# 5_to_var_new.net
KiCad netlist of a schematic drawn in EAGLE
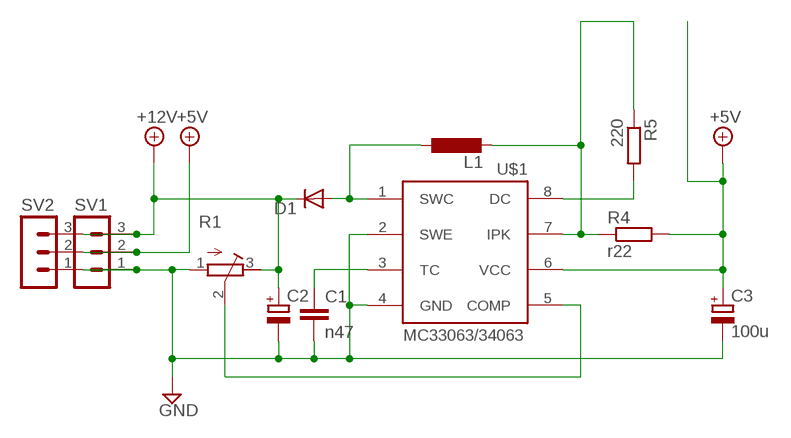
[diagram p0: schematic, sheet 1]

(export (version "E")
  (design (tool "Eeschema 10.0.6"))
  (components
    (comp (ref "C1")
      (value "n47")
      (footprint "eagle-import:C025-025X050")
      (libsource (lib "eagle-import") (part "C-EU025-025X050"))
    )
    (comp (ref "C2")
      (value "CPOL-EUE3.5-8")
      (footprint "eagle-import:E3,5-8")
      (libsource (lib "eagle-import") (part "CPOL-EUE3.5-8"))
    )
    (comp (ref "C3")
      (value "100u")
      (footprint "eagle-import:E2,5-7")
      (libsource (lib "eagle-import") (part "CPOL-EUE2.5-7"))
    )
    (comp (ref "D1")
      (value "DIODE-D-2.5")
      (footprint "eagle-import:D-2.5")
      (libsource (lib "eagle-import") (part "DIODE-D-2.5"))
    )
    (comp (ref "L1")
      (value "L-EU0207/2V")
      (footprint "eagle-import:0207_2V")
      (libsource (lib "eagle-import") (part "L-EU0207/2V"))
    )
    (comp (ref "R1")
      (value "R-TRIMM3296X")
      (footprint "eagle-import:RTRIM3296X")
      (libsource (lib "eagle-import") (part "R-TRIMM3296X"))
    )
    (comp (ref "R4")
      (value "r22")
      (footprint "eagle-import:0207_2V")
      (libsource (lib "eagle-import") (part "R-EU_0207/2V"))
    )
    (comp (ref "R5")
      (value "220")
      (footprint "eagle-import:0207_2V")
      (libsource (lib "eagle-import") (part "R-EU_0207/2V"))
    )
    (comp (ref "SV1")
      (value "MA03-1")
      (footprint "eagle-import:MA03-1")
      (libsource (lib "eagle-import") (part "MA03-1"))
    )
    (comp (ref "SV2")
      (value "MA03-1")
      (footprint "eagle-import:MA03-1")
      (libsource (lib "eagle-import") (part "MA03-1"))
    )
    (comp (ref "U$1")
      (value "MC33063/MC34063P")
      (footprint "eagle-import:DIL08")
      (libsource (lib "eagle-import") (part "MC33063/MC34063P"))
    )
  )
  (nets
    (net (code "1") (name "+5V") (class "Default")
      (node (ref "C3") (pin "+") (pinfunction "+_+") (pintype "passive"))
      (node (ref "R4") (pin "2") (pinfunction "2_2") (pintype "passive"))
      (node (ref "SV1") (pin "2") (pinfunction "2_2") (pintype "passive"))
      (node (ref "SV2") (pin "2") (pinfunction "2_2") (pintype "passive"))
      (node (ref "U$1") (pin "6") (pinfunction "VCC_6") (pintype "power_in"))
    )
    (net (code "2") (name "+12V") (class "Default")
      (node (ref "C2") (pin "+") (pinfunction "+_+") (pintype "passive"))
      (node (ref "D1") (pin "C") (pinfunction "C_C") (pintype "passive"))
      (node (ref "R1") (pin "3") (pinfunction "E_3") (pintype "passive"))
      (node (ref "SV1") (pin "3") (pinfunction "3_3") (pintype "passive"))
      (node (ref "SV2") (pin "3") (pinfunction "3_3") (pintype "passive"))
    )
    (net (code "3") (name "GND") (class "Default")
      (node (ref "C1") (pin "2") (pinfunction "2_2") (pintype "passive"))
      (node (ref "C2") (pin "-") (pinfunction "-_-") (pintype "passive"))
      (node (ref "C3") (pin "-") (pinfunction "-_-") (pintype "passive"))
      (node (ref "R1") (pin "1") (pinfunction "A_1") (pintype "passive"))
      (node (ref "SV1") (pin "1") (pinfunction "1_1") (pintype "passive"))
      (node (ref "SV2") (pin "1") (pinfunction "1_1") (pintype "passive"))
      (node (ref "U$1") (pin "2") (pinfunction "SWE_2") (pintype "input"))
      (node (ref "U$1") (pin "4") (pinfunction "GND_4") (pintype "power_in"))
    )
    (net (code "4") (name "Net-(R1-S)") (class "Default")
      (node (ref "R1") (pin "2") (pinfunction "S_2") (pintype "passive"))
      (node (ref "U$1") (pin "5") (pinfunction "COMP_5") (pintype "input"))
    )
    (net (code "5") (name "Net-(U$1-DC)") (class "Default")
      (node (ref "R5") (pin "2") (pinfunction "2_2") (pintype "passive"))
      (node (ref "U$1") (pin "8") (pinfunction "DC_8") (pintype "input"))
    )
    (net (code "6") (name "Net-(U$1-IPK)") (class "Default")
      (node (ref "L1") (pin "2") (pinfunction "2_2") (pintype "passive"))
      (node (ref "R4") (pin "1") (pinfunction "1_1") (pintype "passive"))
      (node (ref "R5") (pin "1") (pinfunction "1_1") (pintype "passive"))
      (node (ref "U$1") (pin "7") (pinfunction "IPK_7") (pintype "bidirectional"))
    )
    (net (code "7") (name "Net-(U$1-SWC)") (class "Default")
      (node (ref "D1") (pin "A") (pinfunction "A_A") (pintype "passive"))
      (node (ref "L1") (pin "1") (pinfunction "1_1") (pintype "passive"))
      (node (ref "U$1") (pin "1") (pinfunction "SWC_1") (pintype "input"))
    )
    (net (code "8") (name "Net-(U$1-TC)") (class "Default")
      (node (ref "C1") (pin "1") (pinfunction "1_1") (pintype "passive"))
      (node (ref "U$1") (pin "3") (pinfunction "TC_3") (pintype "input"))
    )
  )
)
